# v00_hardware.net
KiCad netlist of a schematic drawn in EAGLE
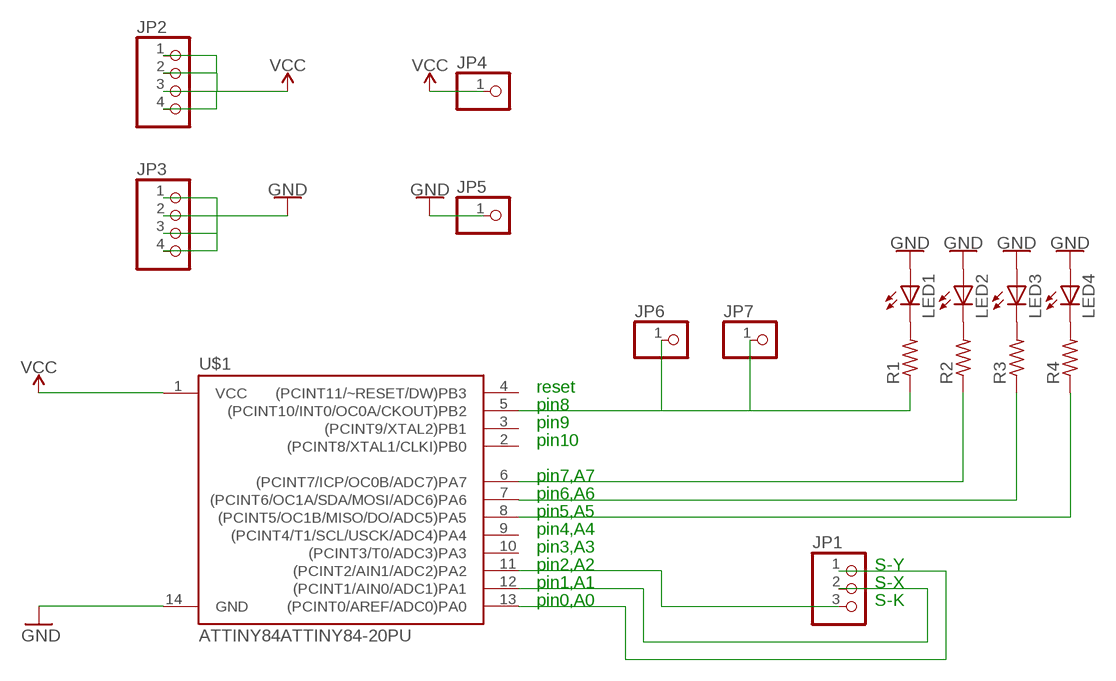
[diagram p0: schematic, sheet 1]

(export (version "E")
  (design (tool "Eeschema 10.0.6"))
  (components
    (comp (ref "JP1")
      (value "PINHD-1X3")
      (footprint "eagle-import:1X03")
      (libsource (lib "eagle-import") (part "PINHD-1X3"))
    )
    (comp (ref "JP2")
      (value "PINHD-1X4")
      (footprint "eagle-import:1X04")
      (libsource (lib "eagle-import") (part "PINHD-1X4"))
    )
    (comp (ref "JP3")
      (value "PINHD-1X4")
      (footprint "eagle-import:1X04")
      (libsource (lib "eagle-import") (part "PINHD-1X4"))
    )
    (comp (ref "JP4")
      (value "PINHD-1X1")
      (footprint "eagle-import:1X01")
      (libsource (lib "eagle-import") (part "PINHD-1X1"))
    )
    (comp (ref "JP5")
      (value "PINHD-1X1")
      (footprint "eagle-import:1X01")
      (libsource (lib "eagle-import") (part "PINHD-1X1"))
    )
    (comp (ref "JP6")
      (value "PINHD-1X1")
      (footprint "eagle-import:1X01")
      (libsource (lib "eagle-import") (part "PINHD-1X1"))
    )
    (comp (ref "JP7")
      (value "PINHD-1X1")
      (footprint "eagle-import:1X01")
      (libsource (lib "eagle-import") (part "PINHD-1X1"))
    )
    (comp (ref "LED1")
      (value "LED5MM")
      (footprint "eagle-import:LED5MM")
      (libsource (lib "eagle-import") (part "LED5MM"))
    )
    (comp (ref "LED2")
      (value "LED5MM")
      (footprint "eagle-import:LED5MM")
      (libsource (lib "eagle-import") (part "LED5MM"))
    )
    (comp (ref "LED3")
      (value "LED5MM")
      (footprint "eagle-import:LED5MM")
      (libsource (lib "eagle-import") (part "LED5MM"))
    )
    (comp (ref "LED4")
      (value "LED5MM")
      (footprint "eagle-import:LED5MM")
      (libsource (lib "eagle-import") (part "LED5MM"))
    )
    (comp (ref "R1")
      (value "R-US_0204/7")
      (footprint "eagle-import:0204_7")
      (libsource (lib "eagle-import") (part "R-US_0204/7"))
    )
    (comp (ref "R2")
      (value "R-US_0204/7")
      (footprint "eagle-import:0204_7")
      (libsource (lib "eagle-import") (part "R-US_0204/7"))
    )
    (comp (ref "R3")
      (value "R-US_0204/7")
      (footprint "eagle-import:0204_7")
      (libsource (lib "eagle-import") (part "R-US_0204/7"))
    )
    (comp (ref "R4")
      (value "R-US_0204/7")
      (footprint "eagle-import:0204_7")
      (libsource (lib "eagle-import") (part "R-US_0204/7"))
    )
    (comp (ref "U$1")
      (value "ATTINY84ATTINY84-20PU")
      (footprint "eagle-import:DIP14")
      (libsource (lib "eagle-import") (part "ATTINY84ATTINY84-20PU"))
    )
  )
  (nets
    (net (code "1") (name "GND") (class "Default")
      (node (ref "JP3") (pin "1") (pinfunction "1_1") (pintype "passive"))
      (node (ref "JP3") (pin "2") (pinfunction "2_2") (pintype "passive"))
      (node (ref "JP3") (pin "3") (pinfunction "3_3") (pintype "passive"))
      (node (ref "JP3") (pin "4") (pinfunction "4_4") (pintype "passive"))
      (node (ref "JP5") (pin "1") (pinfunction "1_1") (pintype "passive"))
      (node (ref "LED1") (pin "A") (pinfunction "A_A") (pintype "passive"))
      (node (ref "LED2") (pin "A") (pinfunction "A_A") (pintype "passive"))
      (node (ref "LED3") (pin "A") (pinfunction "A_A") (pintype "passive"))
      (node (ref "LED4") (pin "A") (pinfunction "A_A") (pintype "passive"))
      (node (ref "U$1") (pin "14") (pinfunction "GND_14") (pintype "bidirectional"))
    )
    (net (code "2") (name "Net-(LED1-C)") (class "Default")
      (node (ref "LED1") (pin "K") (pinfunction "C_K") (pintype "passive"))
      (node (ref "R1") (pin "2") (pinfunction "2_2") (pintype "passive"))
    )
    (net (code "3") (name "Net-(LED2-C)") (class "Default")
      (node (ref "LED2") (pin "K") (pinfunction "C_K") (pintype "passive"))
      (node (ref "R2") (pin "2") (pinfunction "2_2") (pintype "passive"))
    )
    (net (code "4") (name "Net-(LED3-C)") (class "Default")
      (node (ref "LED3") (pin "K") (pinfunction "C_K") (pintype "passive"))
      (node (ref "R3") (pin "2") (pinfunction "2_2") (pintype "passive"))
    )
    (net (code "5") (name "Net-(LED4-C)") (class "Default")
      (node (ref "LED4") (pin "K") (pinfunction "C_K") (pintype "passive"))
      (node (ref "R4") (pin "2") (pinfunction "2_2") (pintype "passive"))
    )
    (net (code "6") (name "Net-(U$1-(PCINT0{slash}AREF{slash}ADC0)PA0)") (class "Default")
      (node (ref "JP1") (pin "1") (pinfunction "1_1") (pintype "passive"))
      (node (ref "U$1") (pin "13") (pinfunction "(PCINT0/AREF/ADC0)PA0_13") (pintype "bidirectional"))
    )
    (net (code "7") (name "Net-(U$1-(PCINT1{slash}AIN0{slash}ADC1)PA1)") (class "Default")
      (node (ref "JP1") (pin "2") (pinfunction "2_2") (pintype "passive"))
      (node (ref "U$1") (pin "12") (pinfunction "(PCINT1/AIN0/ADC1)PA1_12") (pintype "bidirectional"))
    )
    (net (code "8") (name "Net-(U$1-(PCINT2{slash}AIN1{slash}ADC2)PA2)") (class "Default")
      (node (ref "JP1") (pin "3") (pinfunction "3_3") (pintype "passive"))
      (node (ref "U$1") (pin "11") (pinfunction "(PCINT2/AIN1/ADC2)PA2_11") (pintype "bidirectional"))
    )
    (net (code "9") (name "Net-(U$1-(PCINT5{slash}OC1B{slash}MISO{slash}DO{slash}ADC5)PA5)") (class "Default")
      (node (ref "R4") (pin "1") (pinfunction "1_1") (pintype "passive"))
      (node (ref "U$1") (pin "8") (pinfunction "(PCINT5/OC1B/MISO/DO/ADC5)PA5_8") (pintype "bidirectional"))
    )
    (net (code "10") (name "Net-(U$1-(PCINT6{slash}OC1A{slash}SDA{slash}MOSI{slash}ADC6)PA6)") (class "Default")
      (node (ref "R3") (pin "1") (pinfunction "1_1") (pintype "passive"))
      (node (ref "U$1") (pin "7") (pinfunction "(PCINT6/OC1A/SDA/MOSI/ADC6)PA6_7") (pintype "bidirectional"))
    )
    (net (code "11") (name "Net-(U$1-(PCINT7{slash}ICP{slash}OC0B{slash}ADC7)PA7)") (class "Default")
      (node (ref "R2") (pin "1") (pinfunction "1_1") (pintype "passive"))
      (node (ref "U$1") (pin "6") (pinfunction "(PCINT7/ICP/OC0B/ADC7)PA7_6") (pintype "bidirectional"))
    )
    (net (code "12") (name "Net-(U$1-(PCINT10{slash}INT0{slash}OC0A{slash}CKOUT)PB2)") (class "Default")
      (node (ref "JP6") (pin "1") (pinfunction "1_1") (pintype "passive"))
      (node (ref "JP7") (pin "1") (pinfunction "1_1") (pintype "passive"))
      (node (ref "R1") (pin "1") (pinfunction "1_1") (pintype "passive"))
      (node (ref "U$1") (pin "5") (pinfunction "(PCINT10/INT0/OC0A/CKOUT)PB2_5") (pintype "bidirectional"))
    )
    (net (code "13") (name "VCC") (class "Default")
      (node (ref "JP2") (pin "1") (pinfunction "1_1") (pintype "passive"))
      (node (ref "JP2") (pin "2") (pinfunction "2_2") (pintype "passive"))
      (node (ref "JP2") (pin "3") (pinfunction "3_3") (pintype "passive"))
      (node (ref "JP2") (pin "4") (pinfunction "4_4") (pintype "passive"))
      (node (ref "JP4") (pin "1") (pinfunction "1_1") (pintype "passive"))
      (node (ref "U$1") (pin "1") (pinfunction "VCC_1") (pintype "bidirectional"))
    )
    (net (code "14") (name "unconnected-(U$1-(PCINT3{slash}T0{slash}ADC3)PA3-Pad10)") (class "Default")
      (node (ref "U$1") (pin "10") (pinfunction "(PCINT3/T0/ADC3)PA3_10") (pintype "bidirectional"))
    )
    (net (code "15") (name "unconnected-(U$1-(PCINT4{slash}T1{slash}SCL{slash}USCK{slash}ADC4)PA4-Pad9)") (class "Default")
      (node (ref "U$1") (pin "9") (pinfunction "(PCINT4/T1/SCL/USCK/ADC4)PA4_9") (pintype "bidirectional"))
    )
    (net (code "16") (name "unconnected-(U$1-(PCINT8{slash}XTAL1{slash}CLKI)PB0-Pad2)") (class "Default")
      (node (ref "U$1") (pin "2") (pinfunction "(PCINT8/XTAL1/CLKI)PB0_2") (pintype "bidirectional"))
    )
    (net (code "17") (name "unconnected-(U$1-(PCINT9{slash}XTAL2)PB1-Pad3)") (class "Default")
      (node (ref "U$1") (pin "3") (pinfunction "(PCINT9/XTAL2)PB1_3") (pintype "bidirectional"))
    )
    (net (code "18") (name "unconnected-(U$1-(PCINT11{slash}~{RESET{slash}DW})PB3-Pad4)") (class "Default")
      (node (ref "U$1") (pin "4") (pinfunction "(PCINT11/~{RESET/DW})PB3_4") (pintype "bidirectional"))
    )
  )
)
